# frisk-led-test.net
KiCad netlist of a schematic drawn in EAGLE
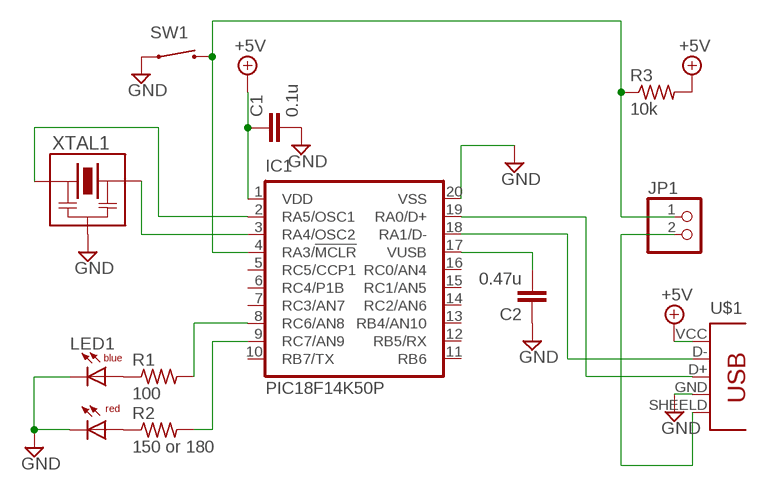
[diagram p0: schematic, sheet 1]

(export (version "E")
  (design (tool "Eeschema 10.0.6"))
  (components
    (comp (ref "C1")
      (value "0.1u")
      (footprint "eagle-import:C025-024X044")
      (libsource (lib "eagle-import") (part "C-EU025-024X044"))
    )
    (comp (ref "C2")
      (value "0.47u")
      (footprint "eagle-import:C075-032X103")
      (libsource (lib "eagle-import") (part "C-EU075-032X103"))
    )
    (comp (ref "IC1")
      (value "PIC18F14K50P")
      (footprint "eagle-import:DIL20")
      (libsource (lib "eagle-import") (part "PIC18F14K50P"))
    )
    (comp (ref "JP1")
      (value "PINHD-1X2")
      (footprint "eagle-import:1X02")
      (libsource (lib "eagle-import") (part "PINHD-1X2"))
    )
    (comp (ref "LED1")
      (value "SML-02")
      (footprint "eagle-import:SML-02")
      (libsource (lib "eagle-import") (part "SML-02"))
    )
    (comp (ref "R1")
      (value "100")
      (footprint "eagle-import:0204_7")
      (libsource (lib "eagle-import") (part "R-US_0204/7"))
    )
    (comp (ref "R2")
      (value "150 or 180")
      (footprint "eagle-import:0204_7")
      (libsource (lib "eagle-import") (part "R-US_0204/7"))
    )
    (comp (ref "R3")
      (value "10k")
      (footprint "eagle-import:0204_7")
      (libsource (lib "eagle-import") (part "R-US_0204/7"))
    )
    (comp (ref "SW1")
      (value "TVBP06")
      (footprint "eagle-import:TVBP06")
      (libsource (lib "eagle-import") (part "TVBP06"))
    )
    (comp (ref "U$1")
      (value "TYPE-A+SHILED")
      (footprint "eagle-import:TYPE-A")
      (libsource (lib "eagle-import") (part "TYPE-A+SHILED"))
    )
    (comp (ref "XTAL1")
      (value "CSTCE12M0G15L")
      (footprint "eagle-import:CSTCE")
      (libsource (lib "eagle-import") (part "CSTCE12M0G15L"))
    )
  )
  (nets
    (net (code "1") (name "+5V") (class "Default")
      (node (ref "C1") (pin "1") (pinfunction "1_1") (pintype "passive"))
      (node (ref "IC1") (pin "1") (pinfunction "VDD_1") (pintype "power_in"))
      (node (ref "R3") (pin "2") (pinfunction "2_2") (pintype "passive"))
      (node (ref "U$1") (pin "VCC") (pinfunction "1_VCC") (pintype "power_in"))
    )
    (net (code "2") (name "GND") (class "Default")
      (node (ref "C1") (pin "2") (pinfunction "2_2") (pintype "passive"))
      (node (ref "C2") (pin "1") (pinfunction "1_1") (pintype "passive"))
      (node (ref "IC1") (pin "20") (pinfunction "VSS_20") (pintype "power_in"))
      (node (ref "LED1") (pin "1") (pinfunction "CC1_1") (pintype "passive"))
      (node (ref "LED1") (pin "3") (pinfunction "CC2_3") (pintype "passive"))
      (node (ref "SW1") (pin "1") (pinfunction "1_1") (pintype "passive"))
      (node (ref "U$1") (pin "GND") (pinfunction "4_GND") (pintype "power_in"))
      (node (ref "XTAL1") (pin "2") (pinfunction "GND_2") (pintype "bidirectional"))
    )
    (net (code "3") (name "Net-(IC1-RA0{slash}D+)") (class "Default")
      (node (ref "IC1") (pin "19") (pinfunction "RA0/D+_19") (pintype "bidirectional"))
      (node (ref "U$1") (pin "D+") (pinfunction "3_D+") (pintype "passive"))
    )
    (net (code "4") (name "Net-(IC1-RA1{slash}D-)") (class "Default")
      (node (ref "IC1") (pin "18") (pinfunction "RA1/D-_18") (pintype "bidirectional"))
      (node (ref "U$1") (pin "D-") (pinfunction "2_D-") (pintype "passive"))
    )
    (net (code "5") (name "Net-(IC1-RA3{slash}~{MCLR})") (class "Default")
      (node (ref "IC1") (pin "4") (pinfunction "RA3/~{MCLR}_4") (pintype "bidirectional"))
      (node (ref "JP1") (pin "1") (pinfunction "1_1") (pintype "passive"))
      (node (ref "R3") (pin "1") (pinfunction "1_1") (pintype "passive"))
      (node (ref "SW1") (pin "2") (pinfunction "2_2") (pintype "passive"))
    )
    (net (code "6") (name "Net-(IC1-RA4{slash}OSC2)") (class "Default")
      (node (ref "IC1") (pin "3") (pinfunction "RA4/OSC2_3") (pintype "bidirectional"))
      (node (ref "XTAL1") (pin "3") (pinfunction "RIT_3") (pintype "bidirectional"))
    )
    (net (code "7") (name "Net-(IC1-RA5{slash}OSC1)") (class "Default")
      (node (ref "IC1") (pin "2") (pinfunction "RA5/OSC1_2") (pintype "bidirectional"))
      (node (ref "XTAL1") (pin "1") (pinfunction "LFT_1") (pintype "bidirectional"))
    )
    (net (code "8") (name "Net-(IC1-RC6{slash}AN8)") (class "Default")
      (node (ref "IC1") (pin "8") (pinfunction "RC6/AN8_8") (pintype "bidirectional"))
      (node (ref "R1") (pin "2") (pinfunction "2_2") (pintype "passive"))
    )
    (net (code "9") (name "Net-(IC1-RC7{slash}AN9)") (class "Default")
      (node (ref "IC1") (pin "9") (pinfunction "RC7/AN9_9") (pintype "bidirectional"))
      (node (ref "R2") (pin "2") (pinfunction "2_2") (pintype "passive"))
    )
    (net (code "10") (name "Net-(IC1-VUSB)") (class "Default")
      (node (ref "C2") (pin "2") (pinfunction "2_2") (pintype "passive"))
      (node (ref "IC1") (pin "17") (pinfunction "VUSB_17") (pintype "bidirectional"))
    )
    (net (code "11") (name "Net-(LED1-AB)") (class "Default")
      (node (ref "LED1") (pin "2") (pinfunction "AB_2") (pintype "passive"))
      (node (ref "R1") (pin "1") (pinfunction "1_1") (pintype "passive"))
    )
    (net (code "12") (name "Net-(LED1-AR)") (class "Default")
      (node (ref "LED1") (pin "4") (pinfunction "AR_4") (pintype "passive"))
      (node (ref "R2") (pin "1") (pinfunction "1_1") (pintype "passive"))
    )
    (net (code "13") (name "Net-(U$1-5)") (class "Default")
      (node (ref "JP1") (pin "2") (pinfunction "2_2") (pintype "passive"))
      (node (ref "U$1") (pin "SHEELD") (pinfunction "5_SHEELD") (pintype "passive"))
    )
    (net (code "14") (name "unconnected-(IC1-RB4{slash}AN10-Pad13)") (class "Default")
      (node (ref "IC1") (pin "13") (pinfunction "RB4/AN10_13") (pintype "bidirectional"))
    )
    (net (code "15") (name "unconnected-(IC1-RB5{slash}RX-Pad12)") (class "Default")
      (node (ref "IC1") (pin "12") (pinfunction "RB5/RX_12") (pintype "bidirectional"))
    )
    (net (code "16") (name "unconnected-(IC1-RB6-Pad11)") (class "Default")
      (node (ref "IC1") (pin "11") (pinfunction "RB6_11") (pintype "bidirectional"))
    )
    (net (code "17") (name "unconnected-(IC1-RB7{slash}TX-Pad10)") (class "Default")
      (node (ref "IC1") (pin "10") (pinfunction "RB7/TX_10") (pintype "bidirectional"))
    )
    (net (code "18") (name "unconnected-(IC1-RC0{slash}AN4-Pad16)") (class "Default")
      (node (ref "IC1") (pin "16") (pinfunction "RC0/AN4_16") (pintype "bidirectional"))
    )
    (net (code "19") (name "unconnected-(IC1-RC1{slash}AN5-Pad15)") (class "Default")
      (node (ref "IC1") (pin "15") (pinfunction "RC1/AN5_15") (pintype "bidirectional"))
    )
    (net (code "20") (name "unconnected-(IC1-RC2{slash}AN6-Pad14)") (class "Default")
      (node (ref "IC1") (pin "14") (pinfunction "RC2/AN6_14") (pintype "bidirectional"))
    )
    (net (code "21") (name "unconnected-(IC1-RC3{slash}AN7-Pad7)") (class "Default")
      (node (ref "IC1") (pin "7") (pinfunction "RC3/AN7_7") (pintype "bidirectional"))
    )
    (net (code "22") (name "unconnected-(IC1-RC4{slash}P1B-Pad6)") (class "Default")
      (node (ref "IC1") (pin "6") (pinfunction "RC4/P1B_6") (pintype "bidirectional"))
    )
    (net (code "23") (name "unconnected-(IC1-RC5{slash}CCP1-Pad5)") (class "Default")
      (node (ref "IC1") (pin "5") (pinfunction "RC5/CCP1_5") (pintype "bidirectional"))
    )
  )
)
